# RobotBooster_mini_v1.net
KiCad netlist of a schematic drawn in EAGLE
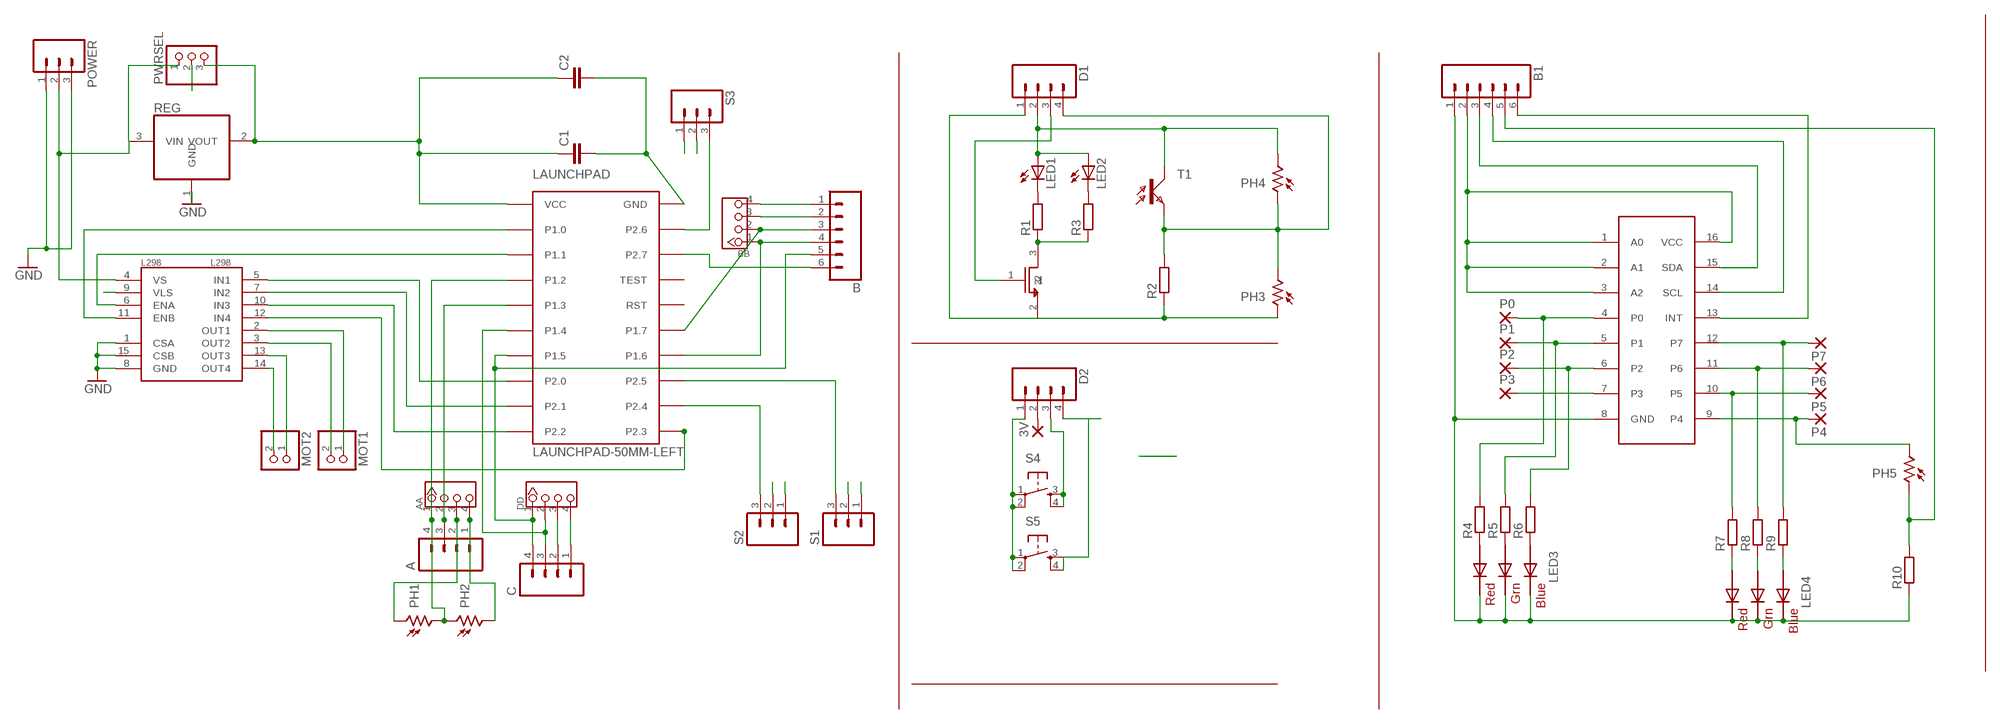
[diagram p0: schematic, sheet 1]

(export (version "E")
  (design (tool "Eeschema 10.0.6"))
  (components
    (comp (ref "3V")
      (value "1,6/0,8")
      (footprint "eagle-import:1,6_0,8")
      (libsource (lib "eagle-import") (part "1,6/0,8"))
    )
    (comp (ref "A")
      (value "M04PTH")
      (footprint "eagle-import:1X04")
      (libsource (lib "eagle-import") (part "M04PTH"))
    )
    (comp (ref "AA")
      (value "TWIG-4P-2.0")
      (footprint "eagle-import:4P-2.0-W_O-BUCKLE")
      (libsource (lib "eagle-import") (part "TWIG-4P-2.0"))
    )
    (comp (ref "B")
      (value "M06SIP")
      (footprint "eagle-import:1X06")
      (libsource (lib "eagle-import") (part "M06SIP"))
    )
    (comp (ref "B1")
      (value "M06SIP")
      (footprint "eagle-import:1X06")
      (libsource (lib "eagle-import") (part "M06SIP"))
    )
    (comp (ref "BB")
      (value "TWIG-4P-2.0")
      (footprint "eagle-import:4P-2.0-W_O-BUCKLE")
      (libsource (lib "eagle-import") (part "TWIG-4P-2.0"))
    )
    (comp (ref "C")
      (value "M04PTH")
      (footprint "eagle-import:1X04")
      (libsource (lib "eagle-import") (part "M04PTH"))
    )
    (comp (ref "C1")
      (value "C-EU025-030X050")
      (footprint "eagle-import:C025-030X050")
      (libsource (lib "eagle-import") (part "C-EU025-030X050"))
    )
    (comp (ref "C2")
      (value "C-EUC1206")
      (footprint "eagle-import:C1206")
      (libsource (lib "eagle-import") (part "C-EUC1206"))
    )
    (comp (ref "D1")
      (value "M04PTH")
      (footprint "eagle-import:1X04")
      (libsource (lib "eagle-import") (part "M04PTH"))
    )
    (comp (ref "D2")
      (value "M04PTH")
      (footprint "eagle-import:1X04")
      (libsource (lib "eagle-import") (part "M04PTH"))
    )
    (comp (ref "DD")
      (value "TWIG-4P-2.0")
      (footprint "eagle-import:4P-2.0-W_O-BUCKLE")
      (libsource (lib "eagle-import") (part "TWIG-4P-2.0"))
    )
    (comp (ref "FET")
      (value "2N7002PW")
      (footprint "eagle-import:SOT323-R")
      (libsource (lib "eagle-import") (part "2N7002PW"))
    )
    (comp (ref "L298")
      (value "L298")
      (footprint "eagle-import:MULTIWATT15")
      (libsource (lib "eagle-import") (part "L298"))
    )
    (comp (ref "LAUNCHPAD")
      (value "LAUNCHPAD-50MM-LEFT")
      (footprint "eagle-import:LAUNCHPAD-50MM-LEFT")
      (libsource (lib "eagle-import") (part "LAUNCHPAD-50MM-LEFT"))
    )
    (comp (ref "LED1")
      (value "LED5MM")
      (footprint "eagle-import:LED5MM")
      (libsource (lib "eagle-import") (part "LED5MM"))
    )
    (comp (ref "LED2")
      (value "LED5MM")
      (footprint "eagle-import:LED5MM")
      (libsource (lib "eagle-import") (part "LED5MM"))
    )
    (comp (ref "LED3")
      (value "RGBLED5050")
      (footprint "eagle-import:RGBLED5050")
      (libsource (lib "eagle-import") (part "RGBLED5050"))
    )
    (comp (ref "LED4")
      (value "RGBLED5050")
      (footprint "eagle-import:RGBLED5050")
      (libsource (lib "eagle-import") (part "RGBLED5050"))
    )
    (comp (ref "MOT1")
      (value "PINHD-1X2")
      (footprint "eagle-import:1X02")
      (libsource (lib "eagle-import") (part "PINHD-1X2"))
    )
    (comp (ref "MOT2")
      (value "PINHD-1X2")
      (footprint "eagle-import:1X02")
      (libsource (lib "eagle-import") (part "PINHD-1X2"))
    )
    (comp (ref "P0")
      (value "1,6/0,8")
      (footprint "eagle-import:1,6_0,8")
      (libsource (lib "eagle-import") (part "1,6/0,8"))
    )
    (comp (ref "P1")
      (value "1,6/0,8")
      (footprint "eagle-import:1,6_0,8")
      (libsource (lib "eagle-import") (part "1,6/0,8"))
    )
    (comp (ref "P2")
      (value "1,6/0,8")
      (footprint "eagle-import:1,6_0,8")
      (libsource (lib "eagle-import") (part "1,6/0,8"))
    )
    (comp (ref "P3")
      (value "1,6/0,8")
      (footprint "eagle-import:1,6_0,8")
      (libsource (lib "eagle-import") (part "1,6/0,8"))
    )
    (comp (ref "P4")
      (value "1,6/0,8")
      (footprint "eagle-import:1,6_0,8")
      (libsource (lib "eagle-import") (part "1,6/0,8"))
    )
    (comp (ref "P5")
      (value "1,6/0,8")
      (footprint "eagle-import:1,6_0,8")
      (libsource (lib "eagle-import") (part "1,6/0,8"))
    )
    (comp (ref "P6")
      (value "1,6/0,8")
      (footprint "eagle-import:1,6_0,8")
      (libsource (lib "eagle-import") (part "1,6/0,8"))
    )
    (comp (ref "P7")
      (value "1,6/0,8")
      (footprint "eagle-import:1,6_0,8")
      (libsource (lib "eagle-import") (part "1,6/0,8"))
    )
    (comp (ref "PH1")
      (value "M9960_11A")
      (footprint "eagle-import:M9960")
      (libsource (lib "eagle-import") (part "M9960_11A"))
    )
    (comp (ref "PH2")
      (value "M9960_11A")
      (footprint "eagle-import:M9960")
      (libsource (lib "eagle-import") (part "M9960_11A"))
    )
    (comp (ref "PH3")
      (value "M9960_11A")
      (footprint "eagle-import:M9960")
      (libsource (lib "eagle-import") (part "M9960_11A"))
    )
    (comp (ref "PH4")
      (value "M9960_11A")
      (footprint "eagle-import:M9960")
      (libsource (lib "eagle-import") (part "M9960_11A"))
    )
    (comp (ref "PH5")
      (value "M9960_11A")
      (footprint "eagle-import:M9960")
      (libsource (lib "eagle-import") (part "M9960_11A"))
    )
    (comp (ref "POWER")
      (value "M03LONGPADS")
      (footprint "eagle-import:1X03_LONGPADS")
      (libsource (lib "eagle-import") (part "M03LONGPADS"))
    )
    (comp (ref "PWRSEL")
      (value "PINHD-1X3")
      (footprint "eagle-import:1X03")
      (libsource (lib "eagle-import") (part "PINHD-1X3"))
    )
    (comp (ref "R1")
      (value "R-EU_R1206")
      (footprint "eagle-import:R1206")
      (libsource (lib "eagle-import") (part "R-EU_R1206"))
    )
    (comp (ref "R2")
      (value "R-EU_R1206")
      (footprint "eagle-import:R1206")
      (libsource (lib "eagle-import") (part "R-EU_R1206"))
    )
    (comp (ref "R3")
      (value "R-EU_R1206")
      (footprint "eagle-import:R1206")
      (libsource (lib "eagle-import") (part "R-EU_R1206"))
    )
    (comp (ref "R4")
      (value "R-EU_R0805")
      (footprint "eagle-import:R0805")
      (libsource (lib "eagle-import") (part "R-EU_R0805"))
    )
    (comp (ref "R5")
      (value "R-EU_R0805")
      (footprint "eagle-import:R0805")
      (libsource (lib "eagle-import") (part "R-EU_R0805"))
    )
    (comp (ref "R6")
      (value "R-EU_R0805")
      (footprint "eagle-import:R0805")
      (libsource (lib "eagle-import") (part "R-EU_R0805"))
    )
    (comp (ref "R7")
      (value "R-EU_R0805")
      (footprint "eagle-import:R0805")
      (libsource (lib "eagle-import") (part "R-EU_R0805"))
    )
    (comp (ref "R8")
      (value "R-EU_R0805")
      (footprint "eagle-import:R0805")
      (libsource (lib "eagle-import") (part "R-EU_R0805"))
    )
    (comp (ref "R9")
      (value "R-EU_R0805")
      (footprint "eagle-import:R0805")
      (libsource (lib "eagle-import") (part "R-EU_R0805"))
    )
    (comp (ref "R10")
      (value "R-EU_R0805")
      (footprint "eagle-import:R0805")
      (libsource (lib "eagle-import") (part "R-EU_R0805"))
    )
    (comp (ref "REG")
      (value "REG1117")
      (footprint "eagle-import:SOT223")
      (libsource (lib "eagle-import") (part "REG1117"))
    )
    (comp (ref "S1")
      (value "M03PTH")
      (footprint "eagle-import:1X03")
      (libsource (lib "eagle-import") (part "M03PTH"))
    )
    (comp (ref "S2")
      (value "M03PTH")
      (footprint "eagle-import:1X03")
      (libsource (lib "eagle-import") (part "M03PTH"))
    )
    (comp (ref "S3")
      (value "M03PTH")
      (footprint "eagle-import:1X03")
      (libsource (lib "eagle-import") (part "M03PTH"))
    )
    (comp (ref "S4")
      (value "TAC_SWITCHPTH")
      (footprint "eagle-import:TACTILE-PTH")
      (libsource (lib "eagle-import") (part "TAC_SWITCHPTH"))
    )
    (comp (ref "S5")
      (value "TAC_SWITCHPTH")
      (footprint "eagle-import:TACTILE-PTH")
      (libsource (lib "eagle-import") (part "TAC_SWITCHPTH"))
    )
    (comp (ref "T1")
      (value "LPT80A")
      (footprint "eagle-import:LPT80A")
      (libsource (lib "eagle-import") (part "LPT80A"))
    )
    (comp (ref "U$1")
      (value "PCA9534DBR")
      (footprint "eagle-import:SSOP16")
      (libsource (lib "eagle-import") (part "PCA9534DBR"))
    )
  )
  (nets
    (net (code "1") (name "/VCC") (class "Default")
      (node (ref "A") (pin "2") (pinfunction "2_2") (pintype "passive"))
      (node (ref "AA") (pin "3") (pinfunction "3_3") (pintype "bidirectional"))
      (node (ref "B") (pin "2") (pinfunction "2_2") (pintype "passive"))
      (node (ref "BB") (pin "3") (pinfunction "3_3") (pintype "bidirectional"))
      (node (ref "C") (pin "2") (pinfunction "2_2") (pintype "passive"))
      (node (ref "C1") (pin "1") (pinfunction "1_1") (pintype "passive"))
      (node (ref "C2") (pin "1") (pinfunction "1_1") (pintype "passive"))
      (node (ref "DD") (pin "3") (pinfunction "3_3") (pintype "bidirectional"))
      (node (ref "L298") (pin "9") (pinfunction "VLS_9") (pintype "bidirectional"))
      (node (ref "LAUNCHPAD") (pin "VCC") (pinfunction "VCC_VCC") (pintype "power_in"))
      (node (ref "PH1") (pin "1") (pinfunction "1_1") (pintype "passive"))
      (node (ref "PWRSEL") (pin "3") (pinfunction "3_3") (pintype "passive"))
      (node (ref "REG") (pin "2") (pinfunction "VOUT_2") (pintype "output"))
    )
    (net (code "2") (name "/VSERV") (class "Default")
      (node (ref "PWRSEL") (pin "2") (pinfunction "2_2") (pintype "passive"))
      (node (ref "S1") (pin "2") (pinfunction "2_2") (pintype "passive"))
      (node (ref "S2") (pin "2") (pinfunction "2_2") (pintype "passive"))
      (node (ref "S3") (pin "2") (pinfunction "2_2") (pintype "passive"))
    )
    (net (code "3") (name "GND") (class "Default")
      (node (ref "A") (pin "1") (pinfunction "1_1") (pintype "passive"))
      (node (ref "AA") (pin "4") (pinfunction "4_4") (pintype "bidirectional"))
      (node (ref "B") (pin "1") (pinfunction "1_1") (pintype "passive"))
      (node (ref "BB") (pin "4") (pinfunction "4_4") (pintype "bidirectional"))
      (node (ref "C") (pin "1") (pinfunction "1_1") (pintype "passive"))
      (node (ref "C1") (pin "2") (pinfunction "2_2") (pintype "passive"))
      (node (ref "C2") (pin "2") (pinfunction "2_2") (pintype "passive"))
      (node (ref "DD") (pin "4") (pinfunction "4_4") (pintype "bidirectional"))
      (node (ref "L298") (pin "1") (pinfunction "CSA_1") (pintype "bidirectional"))
      (node (ref "L298") (pin "15") (pinfunction "CSB_15") (pintype "bidirectional"))
      (node (ref "L298") (pin "8") (pinfunction "GND_8") (pintype "bidirectional"))
      (node (ref "LAUNCHPAD") (pin "GND") (pinfunction "GND_GND") (pintype "power_in"))
      (node (ref "PH2") (pin "2") (pinfunction "2_2") (pintype "passive"))
      (node (ref "POWER") (pin "1") (pinfunction "1_1") (pintype "passive"))
      (node (ref "POWER") (pin "3") (pinfunction "3_3") (pintype "passive"))
      (node (ref "REG") (pin "1") (pinfunction "GND_1") (pintype "power_in"))
      (node (ref "S1") (pin "1") (pinfunction "1_1") (pintype "passive"))
      (node (ref "S2") (pin "1") (pinfunction "1_1") (pintype "passive"))
      (node (ref "S3") (pin "1") (pinfunction "1_1") (pintype "passive"))
    )
    (net (code "4") (name "Net-(3V-P)") (class "Default")
      (node (ref "3V") (pin "1") (pinfunction "P_1") (pintype "passive"))
      (node (ref "D2") (pin "2") (pinfunction "2_2") (pintype "passive"))
    )
    (net (code "5") (name "Net-(A-Pad3)") (class "Default")
      (node (ref "A") (pin "3") (pinfunction "3_3") (pintype "passive"))
      (node (ref "AA") (pin "2") (pinfunction "2_2") (pintype "bidirectional"))
      (node (ref "LAUNCHPAD") (pin "P1.3") (pinfunction "P1.3_P1.3") (pintype "bidirectional"))
    )
    (net (code "6") (name "Net-(A-Pad4)") (class "Default")
      (node (ref "A") (pin "4") (pinfunction "4_4") (pintype "passive"))
      (node (ref "AA") (pin "1") (pinfunction "1_1") (pintype "bidirectional"))
      (node (ref "LAUNCHPAD") (pin "P1.2") (pinfunction "P1.2_P1.2") (pintype "bidirectional"))
      (node (ref "PH1") (pin "2") (pinfunction "2_2") (pintype "passive"))
      (node (ref "PH2") (pin "1") (pinfunction "1_1") (pintype "passive"))
    )
    (net (code "7") (name "Net-(B-Pad3)") (class "Default")
      (node (ref "B") (pin "3") (pinfunction "3_3") (pintype "passive"))
      (node (ref "BB") (pin "2") (pinfunction "2_2") (pintype "bidirectional"))
      (node (ref "LAUNCHPAD") (pin "P1.7") (pinfunction "P1.7_P1.7") (pintype "bidirectional"))
    )
    (net (code "8") (name "Net-(B-Pad4)") (class "Default")
      (node (ref "B") (pin "4") (pinfunction "4_4") (pintype "passive"))
      (node (ref "BB") (pin "1") (pinfunction "1_1") (pintype "bidirectional"))
      (node (ref "LAUNCHPAD") (pin "P1.6") (pinfunction "P1.6_P1.6") (pintype "bidirectional"))
    )
    (net (code "9") (name "Net-(B-Pad5)") (class "Default")
      (node (ref "B") (pin "5") (pinfunction "5_5") (pintype "passive"))
      (node (ref "C") (pin "4") (pinfunction "4_4") (pintype "passive"))
      (node (ref "DD") (pin "1") (pinfunction "1_1") (pintype "bidirectional"))
      (node (ref "LAUNCHPAD") (pin "P1.5") (pinfunction "P1.5_P1.5") (pintype "bidirectional"))
    )
    (net (code "10") (name "Net-(B-Pad6)") (class "Default")
      (node (ref "B") (pin "6") (pinfunction "6_6") (pintype "passive"))
      (node (ref "LAUNCHPAD") (pin "P2.7") (pinfunction "P2.7_P2.7") (pintype "bidirectional"))
    )
    (net (code "11") (name "Net-(B1-Pad5)") (class "Default")
      (node (ref "B1") (pin "5") (pinfunction "5_5") (pintype "passive"))
      (node (ref "PH5") (pin "1") (pinfunction "1_1") (pintype "passive"))
      (node (ref "R10") (pin "2") (pinfunction "2_2") (pintype "passive"))
    )
    (net (code "12") (name "Net-(C-Pad3)") (class "Default")
      (node (ref "C") (pin "3") (pinfunction "3_3") (pintype "passive"))
      (node (ref "DD") (pin "2") (pinfunction "2_2") (pintype "bidirectional"))
      (node (ref "LAUNCHPAD") (pin "P1.4") (pinfunction "P1.4_P1.4") (pintype "bidirectional"))
    )
    (net (code "13") (name "Net-(D1-Pad1)") (class "Default")
      (node (ref "D1") (pin "1") (pinfunction "1_1") (pintype "passive"))
      (node (ref "FET") (pin "2") (pinfunction "2_2") (pintype "bidirectional"))
      (node (ref "PH3") (pin "1") (pinfunction "1_1") (pintype "passive"))
      (node (ref "R2") (pin "1") (pinfunction "1_1") (pintype "passive"))
    )
    (net (code "14") (name "Net-(D1-Pad2)") (class "Default")
      (node (ref "D1") (pin "2") (pinfunction "2_2") (pintype "passive"))
      (node (ref "LED1") (pin "A") (pinfunction "A_A") (pintype "passive"))
      (node (ref "LED2") (pin "A") (pinfunction "A_A") (pintype "passive"))
      (node (ref "PH4") (pin "2") (pinfunction "2_2") (pintype "passive"))
      (node (ref "T1") (pin "C") (pinfunction "C_C") (pintype "passive"))
    )
    (net (code "15") (name "Net-(D1-Pad3)") (class "Default")
      (node (ref "D1") (pin "3") (pinfunction "3_3") (pintype "passive"))
      (node (ref "FET") (pin "1") (pinfunction "1_1") (pintype "bidirectional"))
    )
    (net (code "16") (name "Net-(D1-Pad4)") (class "Default")
      (node (ref "D1") (pin "4") (pinfunction "4_4") (pintype "passive"))
      (node (ref "PH3") (pin "2") (pinfunction "2_2") (pintype "passive"))
      (node (ref "PH4") (pin "1") (pinfunction "1_1") (pintype "passive"))
      (node (ref "R2") (pin "2") (pinfunction "2_2") (pintype "passive"))
      (node (ref "T1") (pin "E") (pinfunction "E_E") (pintype "passive"))
    )
    (net (code "17") (name "Net-(D2-Pad1)") (class "Default")
      (node (ref "D2") (pin "1") (pinfunction "1_1") (pintype "passive"))
      (node (ref "S4") (pin "1") (pinfunction "1_1") (pintype "passive"))
      (node (ref "S4") (pin "2") (pinfunction "2_2") (pintype "passive"))
      (node (ref "S5") (pin "1") (pinfunction "1_1") (pintype "passive"))
      (node (ref "S5") (pin "2") (pinfunction "2_2") (pintype "passive"))
    )
    (net (code "18") (name "Net-(D2-Pad3)") (class "Default")
      (node (ref "D2") (pin "3") (pinfunction "3_3") (pintype "passive"))
      (node (ref "S4") (pin "3") (pinfunction "3_3") (pintype "passive"))
      (node (ref "S4") (pin "4") (pinfunction "4_4") (pintype "passive"))
    )
    (net (code "19") (name "Net-(D2-Pad4)") (class "Default")
      (node (ref "D2") (pin "4") (pinfunction "4_4") (pintype "passive"))
      (node (ref "S5") (pin "3") (pinfunction "3_3") (pintype "passive"))
      (node (ref "S5") (pin "4") (pinfunction "4_4") (pintype "passive"))
    )
    (net (code "20") (name "Net-(FET-Pad3)") (class "Default")
      (node (ref "FET") (pin "3") (pinfunction "3_3") (pintype "bidirectional"))
      (node (ref "R1") (pin "1") (pinfunction "1_1") (pintype "passive"))
      (node (ref "R3") (pin "1") (pinfunction "1_1") (pintype "passive"))
    )
    (net (code "21") (name "Net-(L298-ENA)") (class "Default")
      (node (ref "L298") (pin "6") (pinfunction "ENA_6") (pintype "bidirectional"))
      (node (ref "LAUNCHPAD") (pin "P1.1") (pinfunction "P1.1_P1.1") (pintype "bidirectional"))
    )
    (net (code "22") (name "Net-(L298-ENB)") (class "Default")
      (node (ref "L298") (pin "11") (pinfunction "ENB_11") (pintype "bidirectional"))
      (node (ref "LAUNCHPAD") (pin "P1.0") (pinfunction "P1.0_P1.0") (pintype "bidirectional"))
    )
    (net (code "23") (name "Net-(L298-IN1)") (class "Default")
      (node (ref "L298") (pin "5") (pinfunction "IN1_5") (pintype "bidirectional"))
      (node (ref "LAUNCHPAD") (pin "P2.0") (pinfunction "P2.0_P2.0") (pintype "bidirectional"))
    )
    (net (code "24") (name "Net-(L298-IN2)") (class "Default")
      (node (ref "L298") (pin "7") (pinfunction "IN2_7") (pintype "bidirectional"))
      (node (ref "LAUNCHPAD") (pin "P2.1") (pinfunction "P2.1_P2.1") (pintype "bidirectional"))
    )
    (net (code "25") (name "Net-(L298-IN3)") (class "Default")
      (node (ref "L298") (pin "10") (pinfunction "IN3_10") (pintype "bidirectional"))
      (node (ref "LAUNCHPAD") (pin "P2.2") (pinfunction "P2.2_P2.2") (pintype "bidirectional"))
    )
    (net (code "26") (name "Net-(L298-IN4)") (class "Default")
      (node (ref "L298") (pin "12") (pinfunction "IN4_12") (pintype "bidirectional"))
      (node (ref "LAUNCHPAD") (pin "P2.3") (pinfunction "P2.3_P2.3") (pintype "bidirectional"))
    )
    (net (code "27") (name "Net-(L298-OUT1)") (class "Default")
      (node (ref "L298") (pin "2") (pinfunction "OUT1_2") (pintype "bidirectional"))
      (node (ref "MOT1") (pin "1") (pinfunction "1_1") (pintype "passive"))
    )
    (net (code "28") (name "Net-(L298-OUT2)") (class "Default")
      (node (ref "L298") (pin "3") (pinfunction "OUT2_3") (pintype "bidirectional"))
      (node (ref "MOT1") (pin "2") (pinfunction "2_2") (pintype "passive"))
    )
    (net (code "29") (name "Net-(L298-OUT3)") (class "Default")
      (node (ref "L298") (pin "13") (pinfunction "OUT3_13") (pintype "bidirectional"))
      (node (ref "MOT2") (pin "1") (pinfunction "1_1") (pintype "passive"))
    )
    (net (code "30") (name "Net-(L298-OUT4)") (class "Default")
      (node (ref "L298") (pin "14") (pinfunction "OUT4_14") (pintype "bidirectional"))
      (node (ref "MOT2") (pin "2") (pinfunction "2_2") (pintype "passive"))
    )
    (net (code "31") (name "Net-(L298-VS)") (class "Default")
      (node (ref "L298") (pin "4") (pinfunction "VS_4") (pintype "bidirectional"))
      (node (ref "POWER") (pin "2") (pinfunction "2_2") (pintype "passive"))
      (node (ref "PWRSEL") (pin "1") (pinfunction "1_1") (pintype "passive"))
      (node (ref "REG") (pin "3") (pinfunction "VIN_3") (pintype "input"))
    )
    (net (code "32") (name "Net-(LAUNCHPAD-PadP2.4)") (class "Default")
      (node (ref "LAUNCHPAD") (pin "P2.4") (pinfunction "P2.4_P2.4") (pintype "bidirectional"))
      (node (ref "S2") (pin "3") (pinfunction "3_3") (pintype "passive"))
    )
    (net (code "33") (name "Net-(LAUNCHPAD-PadP2.5)") (class "Default")
      (node (ref "LAUNCHPAD") (pin "P2.5") (pinfunction "P2.5_P2.5") (pintype "bidirectional"))
      (node (ref "S1") (pin "3") (pinfunction "3_3") (pintype "passive"))
    )
    (net (code "34") (name "Net-(LAUNCHPAD-PadP2.6)") (class "Default")
      (node (ref "LAUNCHPAD") (pin "P2.6") (pinfunction "P2.6_P2.6") (pintype "bidirectional"))
      (node (ref "S3") (pin "3") (pinfunction "3_3") (pintype "passive"))
    )
    (net (code "35") (name "Net-(LED1-C)") (class "Default")
      (node (ref "LED1") (pin "K") (pinfunction "C_K") (pintype "passive"))
      (node (ref "R1") (pin "2") (pinfunction "2_2") (pintype "passive"))
    )
    (net (code "36") (name "Net-(LED2-C)") (class "Default")
      (node (ref "LED2") (pin "K") (pinfunction "C_K") (pintype "passive"))
      (node (ref "R3") (pin "2") (pinfunction "2_2") (pintype "passive"))
    )
    (net (code "37") (name "Net-(LED3-BLUE_A)") (class "Default")
      (node (ref "LED3") (pin "3") (pinfunction "BLUE_A_3") (pintype "bidirectional"))
      (node (ref "R6") (pin "1") (pinfunction "1_1") (pintype "passive"))
    )
    (net (code "38") (name "Net-(LED3-BLUE_C)") (class "Default")
      (node (ref "B1") (pin "1") (pinfunction "1_1") (pintype "passive"))
      (node (ref "LED3") (pin "4") (pinfunction "BLUE_C_4") (pintype "bidirectional"))
      (node (ref "LED3") (pin "5") (pinfunction "RED_C_5") (pintype "bidirectional"))
      (node (ref "LED3") (pin "6") (pinfunction "GREEN_C_6") (pintype "bidirectional"))
      (node (ref "LED4") (pin "4") (pinfunction "BLUE_C_4") (pintype "bidirectional"))
      (node (ref "LED4") (pin "5") (pinfunction "RED_C_5") (pintype "bidirectional"))
      (node (ref "LED4") (pin "6") (pinfunction "GREEN_C_6") (pintype "bidirectional"))
      (node (ref "R10") (pin "1") (pinfunction "1_1") (pintype "passive"))
      (node (ref "U$1") (pin "8") (pinfunction "GND_8") (pintype "bidirectional"))
    )
    (net (code "39") (name "Net-(LED3-GREEN_A)") (class "Default")
      (node (ref "LED3") (pin "1") (pinfunction "GREEN_A_1") (pintype "bidirectional"))
      (node (ref "R5") (pin "1") (pinfunction "1_1") (pintype "passive"))
    )
    (net (code "40") (name "Net-(LED3-RED_A)") (class "Default")
      (node (ref "LED3") (pin "2") (pinfunction "RED_A_2") (pintype "bidirectional"))
      (node (ref "R4") (pin "1") (pinfunction "1_1") (pintype "passive"))
    )
    (net (code "41") (name "Net-(LED4-BLUE_A)") (class "Default")
      (node (ref "LED4") (pin "3") (pinfunction "BLUE_A_3") (pintype "bidirectional"))
      (node (ref "R9") (pin "1") (pinfunction "1_1") (pintype "passive"))
    )
    (net (code "42") (name "Net-(LED4-GREEN_A)") (class "Default")
      (node (ref "LED4") (pin "1") (pinfunction "GREEN_A_1") (pintype "bidirectional"))
      (node (ref "R8") (pin "1") (pinfunction "1_1") (pintype "passive"))
    )
    (net (code "43") (name "Net-(LED4-RED_A)") (class "Default")
      (node (ref "LED4") (pin "2") (pinfunction "RED_A_2") (pintype "bidirectional"))
      (node (ref "R7") (pin "1") (pinfunction "1_1") (pintype "passive"))
    )
    (net (code "44") (name "Net-(P0-P)") (class "Default")
      (node (ref "P0") (pin "1") (pinfunction "P_1") (pintype "passive"))
      (node (ref "R4") (pin "2") (pinfunction "2_2") (pintype "passive"))
      (node (ref "U$1") (pin "4") (pinfunction "P0_4") (pintype "bidirectional"))
    )
    (net (code "45") (name "Net-(P1-P)") (class "Default")
      (node (ref "P1") (pin "1") (pinfunction "P_1") (pintype "passive"))
      (node (ref "R5") (pin "2") (pinfunction "2_2") (pintype "passive"))
      (node (ref "U$1") (pin "5") (pinfunction "P1_5") (pintype "bidirectional"))
    )
    (net (code "46") (name "Net-(P2-P)") (class "Default")
      (node (ref "P2") (pin "1") (pinfunction "P_1") (pintype "passive"))
      (node (ref "R6") (pin "2") (pinfunction "2_2") (pintype "passive"))
      (node (ref "U$1") (pin "6") (pinfunction "P2_6") (pintype "bidirectional"))
    )
    (net (code "47") (name "Net-(P3-P)") (class "Default")
      (node (ref "P3") (pin "1") (pinfunction "P_1") (pintype "passive"))
      (node (ref "U$1") (pin "7") (pinfunction "P3_7") (pintype "bidirectional"))
    )
    (net (code "48") (name "Net-(P4-P)") (class "Default")
      (node (ref "P4") (pin "1") (pinfunction "P_1") (pintype "passive"))
      (node (ref "PH5") (pin "2") (pinfunction "2_2") (pintype "passive"))
      (node (ref "U$1") (pin "9") (pinfunction "P4_9") (pintype "bidirectional"))
    )
    (net (code "49") (name "Net-(P5-P)") (class "Default")
      (node (ref "P5") (pin "1") (pinfunction "P_1") (pintype "passive"))
      (node (ref "R7") (pin "2") (pinfunction "2_2") (pintype "passive"))
      (node (ref "U$1") (pin "10") (pinfunction "P5_10") (pintype "bidirectional"))
    )
    (net (code "50") (name "Net-(P6-P)") (class "Default")
      (node (ref "P6") (pin "1") (pinfunction "P_1") (pintype "passive"))
      (node (ref "R8") (pin "2") (pinfunction "2_2") (pintype "passive"))
      (node (ref "U$1") (pin "11") (pinfunction "P6_11") (pintype "bidirectional"))
    )
    (net (code "51") (name "Net-(P7-P)") (class "Default")
      (node (ref "P7") (pin "1") (pinfunction "P_1") (pintype "passive"))
      (node (ref "R9") (pin "2") (pinfunction "2_2") (pintype "passive"))
      (node (ref "U$1") (pin "12") (pinfunction "P7_12") (pintype "bidirectional"))
    )
    (net (code "52") (name "Net-(U$1-A0)") (class "Default")
      (node (ref "B1") (pin "2") (pinfunction "2_2") (pintype "passive"))
      (node (ref "U$1") (pin "1") (pinfunction "A0_1") (pintype "bidirectional"))
      (node (ref "U$1") (pin "16") (pinfunction "VCC_16") (pintype "bidirectional"))
      (node (ref "U$1") (pin "2") (pinfunction "A1_2") (pintype "bidirectional"))
      (node (ref "U$1") (pin "3") (pinfunction "A2_3") (pintype "bidirectional"))
    )
    (net (code "53") (name "Net-(U$1-INT)") (class "Default")
      (node (ref "B1") (pin "6") (pinfunction "6_6") (pintype "passive"))
      (node (ref "U$1") (pin "13") (pinfunction "INT_13") (pintype "bidirectional"))
    )
    (net (code "54") (name "Net-(U$1-SCL)") (class "Default")
      (node (ref "B1") (pin "4") (pinfunction "4_4") (pintype "passive"))
      (node (ref "U$1") (pin "14") (pinfunction "SCL_14") (pintype "bidirectional"))
    )
    (net (code "55") (name "Net-(U$1-SDA)") (class "Default")
      (node (ref "B1") (pin "3") (pinfunction "3_3") (pintype "passive"))
      (node (ref "U$1") (pin "15") (pinfunction "SDA_15") (pintype "bidirectional"))
    )
    (net (code "56") (name "unconnected-(LAUNCHPAD-PadRST)") (class "Default")
      (node (ref "LAUNCHPAD") (pin "RST") (pinfunction "RST_RST") (pintype "bidirectional"))
    )
    (net (code "57") (name "unconnected-(LAUNCHPAD-PadTEST)") (class "Default")
      (node (ref "LAUNCHPAD") (pin "TEST") (pinfunction "TEST_TEST") (pintype "bidirectional"))
    )
  )
)
